# Cell_Monitor_12S_V0_1.net
KiCad netlist of a schematic drawn in Altium Designer
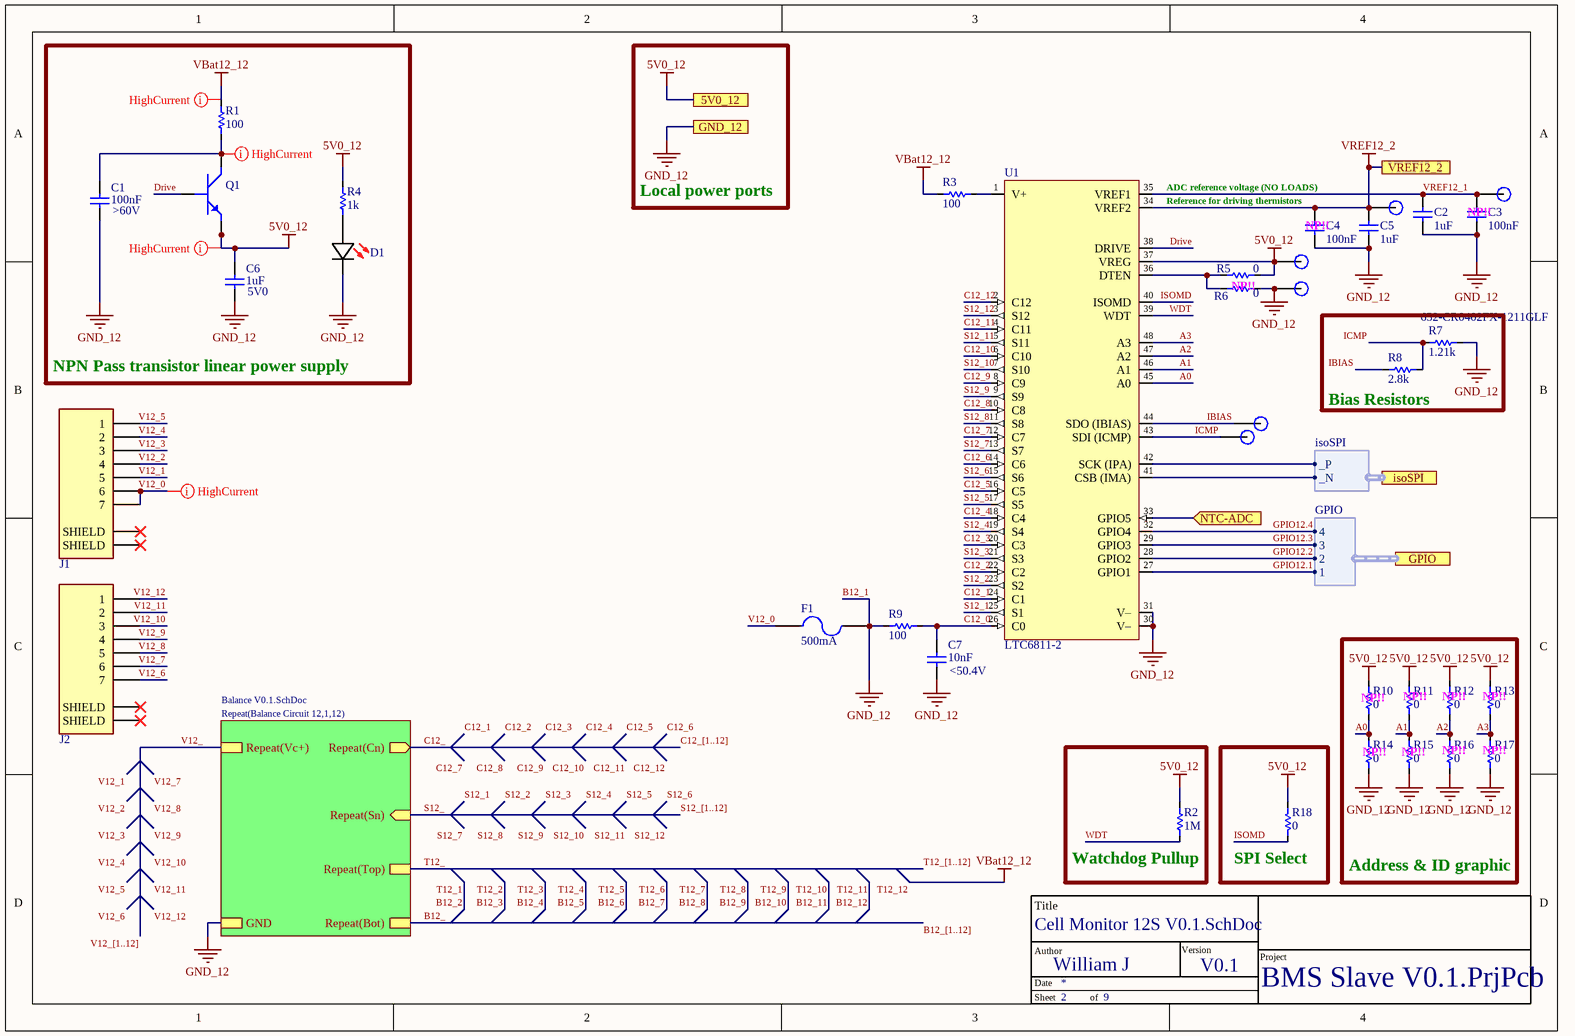
[diagram p0: Cell Monitor 12S V0.1.SchDoc]

(export (version "E")
  (design (tool "Eeschema 10.0.6"))
  (components
    (comp (ref "C1")
      (value "100nF")
      (footprint "C_0402")
      (description "Capacitor")
      (fields (field (name "VOLTAGE") ">60V") (field (name "Comment") "GRM155R62A104KE14D"))
      (libsource (lib "Passives") (part "Capacitor"))
    )
    (comp (ref "C2")
      (value "1uF")
      (footprint "C_0402")
      (description "Capacitor")
      (fields (field (name "Comment") "EMK105BJ105KV-F"))
      (libsource (lib "Passives") (part "Capacitor"))
    )
    (comp (ref "C3")
      (value "100nF")
      (footprint "C_0402")
      (description "Capacitor")
      (fields (field (name "Comment") "GRM155R62A104KE14D"))
      (libsource (lib "Passives") (part "Capacitor"))
    )
    (comp (ref "C4")
      (value "100nF")
      (footprint "C_0402")
      (description "Capacitor")
      (fields (field (name "Comment") "GRM155R62A104KE14D"))
      (libsource (lib "Passives") (part "Capacitor"))
    )
    (comp (ref "C5")
      (value "1uF")
      (footprint "C_0402")
      (description "Capacitor")
      (fields (field (name "Comment") "EMK105BJ105KV-F"))
      (libsource (lib "Passives") (part "Capacitor"))
    )
    (comp (ref "C6")
      (value "1uF")
      (footprint "C_0402")
      (description "Capacitor")
      (fields (field (name "VOLTAGE") "5V0") (field (name "Comment") "EMK105BJ105KV-F"))
      (libsource (lib "Passives") (part "Capacitor"))
    )
    (comp (ref "C7")
      (value "10nF")
      (footprint "C_0402")
      (description "Capacitor")
      (fields (field (name "VOLTAGE") "<50.4V") (field (name "Comment") "C1005X7S2A103K050BB"))
      (libsource (lib "Passives") (part "Capacitor"))
    )
    (comp (ref "D1")
      (value "150060SS55040")
      (footprint "LED (0603)")
      (description "LED RED DIFFUSED 0603 SMD")
      (fields (field (name "MANUFACTURER") "Wurth Electronics"))
      (libsource (lib "LEDLib") (part "150060SS55040"))
    )
    (comp (ref "F1")
      (value "0466.500NR")
      (footprint "0466.500NR")
      (fields
        (field (name "MANUFACTURER") "Littelfuse")
        (field (name "CURRENT RATING") "500mA")
        (field (name "PUBLISHER") "Altium Limited")
      )
      (libsource (lib "Miscellaneous Devices") (part "Fuse 2"))
    )
    (comp (ref "J1")
      (value "84953-7")
      (footprint "84953-7")
      (fields (field (name "MANUFACTURER") "TE Connectivity"))
      (libsource (lib "TE_Con") (part "84953-7"))
    )
    (comp (ref "J2")
      (value "84953-7")
      (footprint "84953-7")
      (fields (field (name "MANUFACTURER") "TE Connectivity"))
      (libsource (lib "TE_Con") (part "84953-7"))
    )
    (comp (ref "NT1") (value "NetTie") (footprint "NetTie") (libsource (lib "SchematicLib") (part "NetTie")))
    (comp (ref "NT2") (value "NetTie") (footprint "NetTie") (libsource (lib "SchematicLib") (part "NetTie")))
    (comp (ref "Q1")
      (value "PHPT60603NYX")
      (footprint "LFPAK56 (SOT669)")
      (description "60V, 3 A NPN high power bipolar transistor")
      (libsource (lib "SchematicLib") (part "PHPT60603NYX"))
    )
    (comp (ref "R1")
      (value "100")
      (footprint "R_2010")
      (description "Resistor")
      (fields (field (name "Comment") "CRM2010-FX-1000ELF"))
      (libsource (lib "Passives") (part "Resistor"))
    )
    (comp (ref "R2")
      (value "1M")
      (footprint "R_0402")
      (description "Resistor")
      (fields (field (name "Comment") "RC0402JR-071ML"))
      (libsource (lib "Passives") (part "Resistor"))
    )
    (comp (ref "R3")
      (value "100")
      (footprint "R_2010")
      (description "Resistor")
      (fields (field (name "Comment") "CRM2010-FX-1000ELF"))
      (libsource (lib "Passives") (part "Resistor"))
    )
    (comp (ref "R4")
      (value "1k")
      (footprint "R_0402")
      (description "Resistor")
      (fields (field (name "Comment") "RC0402FR-071KL"))
      (libsource (lib "Passives") (part "Resistor"))
    )
    (comp (ref "R5")
      (value "0")
      (footprint "R_0402")
      (description "Resistor")
      (fields (field (name "Comment") "CR0402-J/-000GLF"))
      (libsource (lib "Passives") (part "Resistor"))
    )
    (comp (ref "R6")
      (value "0")
      (footprint "R_0402")
      (description "Resistor")
      (fields (field (name "Comment") "CR0402-J/-000GLF"))
      (libsource (lib "Passives") (part "Resistor"))
    )
    (comp (ref "R7")
      (value "1.21k")
      (footprint "R_0402")
      (description "Resistor")
      (fields
        (field (name "SUPPLIER PART NUMBER 1") "652-CR0402FX-1211GLF")
        (field (name "Comment") "CR0402-FX-1211GLF")
      )
      (libsource (lib "Passives") (part "Resistor"))
    )
    (comp (ref "R8")
      (value "2.8k")
      (footprint "R_0402")
      (description "Resistor")
      (fields (field (name "Comment") "ERJ-2RKF2801X"))
      (libsource (lib "Passives") (part "Resistor"))
    )
    (comp (ref "R9")
      (value "100")
      (footprint "R_0402")
      (description "Resistor")
      (fields (field (name "Comment") "RC0402FR-07100RL"))
      (libsource (lib "Passives") (part "Resistor"))
    )
    (comp (ref "R10")
      (value "0")
      (footprint "R_0402")
      (description "Resistor")
      (fields (field (name "Comment") "CR0402-J/-000GLF"))
      (libsource (lib "Passives") (part "Resistor"))
    )
    (comp (ref "R11")
      (value "0")
      (footprint "R_0402")
      (description "Resistor")
      (fields (field (name "Comment") "CR0402-J/-000GLF"))
      (libsource (lib "Passives") (part "Resistor"))
    )
    (comp (ref "R12")
      (value "0")
      (footprint "R_0402")
      (description "Resistor")
      (fields (field (name "Comment") "CR0402-J/-000GLF"))
      (libsource (lib "Passives") (part "Resistor"))
    )
    (comp (ref "R13")
      (value "0")
      (footprint "R_0402")
      (description "Resistor")
      (fields (field (name "Comment") "CR0402-J/-000GLF"))
      (libsource (lib "Passives") (part "Resistor"))
    )
    (comp (ref "R14")
      (value "0")
      (footprint "R_0402")
      (description "Resistor")
      (fields (field (name "Comment") "CR0402-J/-000GLF"))
      (libsource (lib "Passives") (part "Resistor"))
    )
    (comp (ref "R15")
      (value "0")
      (footprint "R_0402")
      (description "Resistor")
      (fields (field (name "Comment") "CR0402-J/-000GLF"))
      (libsource (lib "Passives") (part "Resistor"))
    )
    (comp (ref "R16")
      (value "0")
      (footprint "R_0402")
      (description "Resistor")
      (fields (field (name "Comment") "CR0402-J/-000GLF"))
      (libsource (lib "Passives") (part "Resistor"))
    )
    (comp (ref "R17")
      (value "0")
      (footprint "R_0402")
      (description "Resistor")
      (fields (field (name "Comment") "CR0402-J/-000GLF"))
      (libsource (lib "Passives") (part "Resistor"))
    )
    (comp (ref "R18")
      (value "0")
      (footprint "R_0402")
      (description "Resistor")
      (fields (field (name "Comment") "CR0402-J/-000GLF"))
      (libsource (lib "Passives") (part "Resistor"))
    )
    (comp (ref "TP1")
      (value "VREF1")
      (footprint "Test Point")
      (description "1.2mm Test point")
      (libsource (lib "SchematicLib") (part "Test Point"))
    )
    (comp (ref "TP2")
      (value "VREF2")
      (footprint "Test Point")
      (description "1.2mm Test point")
      (libsource (lib "SchematicLib") (part "Test Point"))
    )
    (comp (ref "TP3")
      (value "5V0_12")
      (footprint "Test Point")
      (description "1.2mm Test point")
      (libsource (lib "SchematicLib") (part "Test Point"))
    )
    (comp (ref "TP4")
      (value "IBIAS")
      (footprint "Test Point")
      (description "1.2mm Test point")
      (libsource (lib "SchematicLib") (part "Test Point"))
    )
    (comp (ref "TP5")
      (value "ICMP")
      (footprint "Test Point")
      (description "1.2mm Test point")
      (libsource (lib "SchematicLib") (part "Test Point"))
    )
    (comp (ref "TP13")
      (value "5V0_8R")
      (footprint "Test Point")
      (description "1.2mm Test point")
      (libsource (lib "SchematicLib") (part "Test Point"))
    )
    (comp (ref "U1")
      (value "LTC6811-2")
      (footprint "SSOP50P780X200-48N")
      (description "12 Channel Multicell Battery Monitor with Addressable Interface")
      (libsource (lib "SchematicLib") (part "LTC6811-2"))
    )
  )
  (nets
    (net (code "3") (name "/A0") (class "Default")
      (node (ref "R10") (pin "1") (pinfunction "1_1") (pintype "passive"))
      (node (ref "R14") (pin "2") (pinfunction "2_2") (pintype "passive"))
      (node (ref "U1") (pin "45") (pinfunction "A0_45") (pintype "passive"))
    )
    (net (code "4") (name "/A1") (class "Default")
      (node (ref "R11") (pin "1") (pinfunction "1_1") (pintype "passive"))
      (node (ref "R15") (pin "2") (pinfunction "2_2") (pintype "passive"))
      (node (ref "U1") (pin "46") (pinfunction "A1_46") (pintype "passive"))
    )
    (net (code "5") (name "/A2") (class "Default")
      (node (ref "R12") (pin "1") (pinfunction "1_1") (pintype "passive"))
      (node (ref "R16") (pin "2") (pinfunction "2_2") (pintype "passive"))
      (node (ref "U1") (pin "47") (pinfunction "A2_47") (pintype "passive"))
    )
    (net (code "6") (name "/A3") (class "Default")
      (node (ref "R13") (pin "1") (pinfunction "1_1") (pintype "passive"))
      (node (ref "R17") (pin "2") (pinfunction "2_2") (pintype "passive"))
      (node (ref "U1") (pin "48") (pinfunction "A3_48") (pintype "passive"))
    )
    (net (code "8") (name "/B12_1") (class "Default") (node (ref "NT1") (pin "2") (pintype "passive")))
    (net (code "22") (name "/C12_0") (class "Default")
      (node (ref "C7") (pin "2") (pinfunction "2_2") (pintype "passive"))
      (node (ref "R9") (pin "2") (pinfunction "2_2") (pintype "passive"))
      (node (ref "U1") (pin "26") (pinfunction "C0_26") (pintype "input"))
    )
    (net (code "23") (name "/C12_1") (class "Default")
      (node (ref "U1") (pin "24") (pinfunction "C1_24") (pintype "input"))
    )
    (net (code "24") (name "/C12_2") (class "Default")
      (node (ref "U1") (pin "22") (pinfunction "C2_22") (pintype "input"))
    )
    (net (code "25") (name "/C12_3") (class "Default")
      (node (ref "U1") (pin "20") (pinfunction "C3_20") (pintype "input"))
    )
    (net (code "26") (name "/C12_4") (class "Default")
      (node (ref "U1") (pin "18") (pinfunction "C4_18") (pintype "input"))
    )
    (net (code "27") (name "/C12_5") (class "Default")
      (node (ref "U1") (pin "16") (pinfunction "C5_16") (pintype "input"))
    )
    (net (code "28") (name "/C12_6") (class "Default")
      (node (ref "U1") (pin "14") (pinfunction "C6_14") (pintype "input"))
    )
    (net (code "29") (name "/C12_7") (class "Default")
      (node (ref "U1") (pin "12") (pinfunction "C7_12") (pintype "input"))
    )
    (net (code "30") (name "/C12_8") (class "Default")
      (node (ref "U1") (pin "10") (pinfunction "C8_10") (pintype "input"))
    )
    (net (code "31") (name "/C12_9") (class "Default")
      (node (ref "U1") (pin "8") (pinfunction "C9_8") (pintype "input"))
    )
    (net (code "32") (name "/C12_10") (class "Default")
      (node (ref "U1") (pin "6") (pinfunction "C10_6") (pintype "input"))
    )
    (net (code "33") (name "/C12_11") (class "Default")
      (node (ref "U1") (pin "4") (pinfunction "C11_4") (pintype "input"))
    )
    (net (code "34") (name "/C12_12") (class "Default")
      (node (ref "U1") (pin "2") (pinfunction "C12_2") (pintype "input"))
    )
    (net (code "36") (name "/Drive") (class "Default")
      (node (ref "Q1") (pin "4") (pinfunction "Base_4") (pintype "passive"))
      (node (ref "U1") (pin "38") (pinfunction "DRIVE_38") (pintype "passive"))
    )
    (net (code "37") (name "/GPIO12.1") (class "Default")
      (node (ref "U1") (pin "27") (pinfunction "GPIO1_27") (pintype "bidirectional"))
    )
    (net (code "38") (name "/GPIO12.2") (class "Default")
      (node (ref "U1") (pin "28") (pinfunction "GPIO2_28") (pintype "bidirectional"))
    )
    (net (code "39") (name "/GPIO12.3") (class "Default")
      (node (ref "U1") (pin "29") (pinfunction "GPIO3_29") (pintype "bidirectional"))
    )
    (net (code "40") (name "/GPIO12.4") (class "Default")
      (node (ref "U1") (pin "32") (pinfunction "GPIO4_32") (pintype "bidirectional"))
    )
    (net (code "41") (name "/IBIAS") (class "Default")
      (node (ref "R8") (pin "1") (pinfunction "1_1") (pintype "passive"))
      (node (ref "TP4") (pin "1") (pinfunction "1_1") (pintype "passive"))
      (node (ref "U1") (pin "44") (pinfunction "SDO_(IBIAS)_44") (pintype "passive"))
    )
    (net (code "42") (name "/ICMP") (class "Default")
      (node (ref "R7") (pin "1") (pinfunction "1_1") (pintype "passive"))
      (node (ref "R8") (pin "2") (pinfunction "2_2") (pintype "passive"))
      (node (ref "TP5") (pin "1") (pinfunction "1_1") (pintype "passive"))
      (node (ref "U1") (pin "43") (pinfunction "SDI_(ICMP)_43") (pintype "passive"))
    )
    (net (code "43") (name "/ISOMD") (class "Default")
      (node (ref "R18") (pin "1") (pinfunction "1_1") (pintype "passive"))
      (node (ref "U1") (pin "40") (pinfunction "ISOMD_40") (pintype "passive"))
    )
    (net (code "44") (name "/NTC-ADC") (class "Default")
      (node (ref "U1") (pin "33") (pinfunction "GPIO5_33") (pintype "input"))
    )
    (net (code "46") (name "/S12_1") (class "Default")
      (node (ref "U1") (pin "25") (pinfunction "S1_25") (pintype "output"))
    )
    (net (code "47") (name "/S12_2") (class "Default")
      (node (ref "U1") (pin "23") (pinfunction "S2_23") (pintype "output"))
    )
    (net (code "48") (name "/S12_3") (class "Default")
      (node (ref "U1") (pin "21") (pinfunction "S3_21") (pintype "output"))
    )
    (net (code "49") (name "/S12_4") (class "Default")
      (node (ref "U1") (pin "19") (pinfunction "S4_19") (pintype "output"))
    )
    (net (code "50") (name "/S12_5") (class "Default")
      (node (ref "U1") (pin "17") (pinfunction "S5_17") (pintype "output"))
    )
    (net (code "51") (name "/S12_6") (class "Default")
      (node (ref "U1") (pin "15") (pinfunction "S6_15") (pintype "output"))
    )
    (net (code "52") (name "/S12_7") (class "Default")
      (node (ref "U1") (pin "13") (pinfunction "S7_13") (pintype "output"))
    )
    (net (code "53") (name "/S12_8") (class "Default")
      (node (ref "U1") (pin "11") (pinfunction "S8_11") (pintype "output"))
    )
    (net (code "54") (name "/S12_9") (class "Default")
      (node (ref "U1") (pin "9") (pinfunction "S9_9") (pintype "output"))
    )
    (net (code "55") (name "/S12_10") (class "Default")
      (node (ref "U1") (pin "7") (pinfunction "S10_7") (pintype "output"))
    )
    (net (code "56") (name "/S12_11") (class "Default")
      (node (ref "U1") (pin "5") (pinfunction "S11_5") (pintype "output"))
    )
    (net (code "57") (name "/S12_12") (class "Default")
      (node (ref "U1") (pin "3") (pinfunction "S12_3") (pintype "output"))
    )
    (net (code "60") (name "/T12_12") (class "Default") (node (ref "NT2") (pin "1") (pintype "passive")))
    (net (code "63") (name "/V12_0") (class "Default")
      (node (ref "F1") (pin "1") (pinfunction "1_1") (pintype "passive"))
      (node (ref "J1") (pin "6") (pinfunction "6_6") (pintype "passive"))
      (node (ref "J1") (pin "7") (pinfunction "7_7") (pintype "passive"))
    )
    (net (code "64") (name "/V12_1") (class "Default")
      (node (ref "J1") (pin "5") (pinfunction "5_5") (pintype "passive"))
    )
    (net (code "65") (name "/V12_2") (class "Default")
      (node (ref "J1") (pin "4") (pinfunction "4_4") (pintype "passive"))
    )
    (net (code "66") (name "/V12_3") (class "Default")
      (node (ref "J1") (pin "3") (pinfunction "3_3") (pintype "passive"))
    )
    (net (code "67") (name "/V12_4") (class "Default")
      (node (ref "J1") (pin "2") (pinfunction "2_2") (pintype "passive"))
    )
    (net (code "68") (name "/V12_5") (class "Default")
      (node (ref "J1") (pin "1") (pinfunction "1_1") (pintype "passive"))
    )
    (net (code "69") (name "/V12_6") (class "Default")
      (node (ref "J2") (pin "7") (pinfunction "7_7") (pintype "passive"))
    )
    (net (code "70") (name "/V12_7") (class "Default")
      (node (ref "J2") (pin "6") (pinfunction "6_6") (pintype "passive"))
    )
    (net (code "71") (name "/V12_8") (class "Default")
      (node (ref "J2") (pin "5") (pinfunction "5_5") (pintype "passive"))
    )
    (net (code "72") (name "/V12_9") (class "Default")
      (node (ref "J2") (pin "4") (pinfunction "4_4") (pintype "passive"))
    )
    (net (code "73") (name "/V12_10") (class "Default")
      (node (ref "J2") (pin "3") (pinfunction "3_3") (pintype "passive"))
    )
    (net (code "74") (name "/V12_11") (class "Default")
      (node (ref "J2") (pin "2") (pinfunction "2_2") (pintype "passive"))
    )
    (net (code "75") (name "/V12_12") (class "Default")
      (node (ref "J2") (pin "1") (pinfunction "1_1") (pintype "passive"))
    )
    (net (code "77") (name "/VREF12_1") (class "Default")
      (node (ref "C2") (pin "2") (pinfunction "2_2") (pintype "passive"))
      (node (ref "C3") (pin "2") (pinfunction "2_2") (pintype "passive"))
      (node (ref "TP1") (pin "1") (pinfunction "1_1") (pintype "passive"))
      (node (ref "U1") (pin "35") (pinfunction "VREF1_35") (pintype "power_in"))
    )
    (net (code "78") (name "/WDT") (class "Default")
      (node (ref "R2") (pin "1") (pinfunction "1_1") (pintype "passive"))
      (node (ref "U1") (pin "39") (pinfunction "WDT_39") (pintype "passive"))
    )
    (net (code "79") (name "/_N") (class "Default")
      (node (ref "U1") (pin "41") (pinfunction "CSB_(IMA)_41") (pintype "bidirectional"))
    )
    (net (code "80") (name "/_P") (class "Default")
      (node (ref "U1") (pin "42") (pinfunction "SCK_(IPA)_42") (pintype "bidirectional"))
    )
    (net (code "83") (name "5V0_12") (class "Default")
      (node (ref "C6") (pin "2") (pinfunction "2_2") (pintype "passive"))
      (node (ref "Q1") (pin "1") (pinfunction "Emitter_1") (pintype "passive"))
      (node (ref "Q1") (pin "2") (pinfunction "Emitter_2") (pintype "passive"))
      (node (ref "Q1") (pin "3") (pinfunction "Emitter_3") (pintype "passive"))
      (node (ref "R10") (pin "2") (pinfunction "2_2") (pintype "passive"))
      (node (ref "R11") (pin "2") (pinfunction "2_2") (pintype "passive"))
      (node (ref "R12") (pin "2") (pinfunction "2_2") (pintype "passive"))
      (node (ref "R13") (pin "2") (pinfunction "2_2") (pintype "passive"))
      (node (ref "R18") (pin "2") (pinfunction "2_2") (pintype "passive"))
      (node (ref "R2") (pin "2") (pinfunction "2_2") (pintype "passive"))
      (node (ref "R4") (pin "2") (pinfunction "2_2") (pintype "passive"))
      (node (ref "R5") (pin "2") (pinfunction "2_2") (pintype "passive"))
      (node (ref "TP3") (pin "1") (pinfunction "1_1") (pintype "passive"))
      (node (ref "U1") (pin "37") (pinfunction "VREG_37") (pintype "power_in"))
    )
    (net (code "84") (name "GND_12") (class "Default")
      (node (ref "C1") (pin "1") (pinfunction "1_1") (pintype "passive"))
      (node (ref "C2") (pin "1") (pinfunction "1_1") (pintype "passive"))
      (node (ref "C3") (pin "1") (pinfunction "1_1") (pintype "passive"))
      (node (ref "C4") (pin "1") (pinfunction "1_1") (pintype "passive"))
      (node (ref "C5") (pin "1") (pinfunction "1_1") (pintype "passive"))
      (node (ref "C6") (pin "1") (pinfunction "1_1") (pintype "passive"))
      (node (ref "C7") (pin "1") (pinfunction "1_1") (pintype "passive"))
      (node (ref "D1") (pin "1") (pinfunction "K_1") (pintype "passive"))
      (node (ref "F1") (pin "2") (pinfunction "2_2") (pintype "passive"))
      (node (ref "NT1") (pin "1") (pintype "passive"))
      (node (ref "R14") (pin "1") (pinfunction "1_1") (pintype "passive"))
      (node (ref "R15") (pin "1") (pinfunction "1_1") (pintype "passive"))
      (node (ref "R16") (pin "1") (pinfunction "1_1") (pintype "passive"))
      (node (ref "R17") (pin "1") (pinfunction "1_1") (pintype "passive"))
      (node (ref "R6") (pin "1") (pinfunction "1_1") (pintype "passive"))
      (node (ref "R7") (pin "2") (pinfunction "2_2") (pintype "passive"))
      (node (ref "R9") (pin "1") (pinfunction "1_1") (pintype "passive"))
      (node (ref "TP13") (pin "1") (pinfunction "1_1") (pintype "passive"))
      (node (ref "U1") (pin "30") (pinfunction "V–_30") (pintype "power_in"))
      (node (ref "U1") (pin "31") (pinfunction "V–_31") (pintype "power_in"))
    )
    (net (code "85") (name "Net-(D1-A)") (class "Default")
      (node (ref "D1") (pin "2") (pinfunction "A_2") (pintype "passive"))
      (node (ref "R4") (pin "1") (pinfunction "1_1") (pintype "passive"))
    )
    (net (code "86") (name "Net-(Q1-Collector)") (class "Default")
      (node (ref "C1") (pin "2") (pinfunction "2_2") (pintype "passive"))
      (node (ref "Q1") (pin "5") (pinfunction "Collector_5") (pintype "passive"))
      (node (ref "R1") (pin "1") (pinfunction "1_1") (pintype "passive"))
    )
    (net (code "87") (name "Net-(U1-DTEN)") (class "Default")
      (node (ref "R5") (pin "1") (pinfunction "1_1") (pintype "passive"))
      (node (ref "R6") (pin "2") (pinfunction "2_2") (pintype "passive"))
      (node (ref "U1") (pin "36") (pinfunction "DTEN_36") (pintype "passive"))
    )
    (net (code "88") (name "Net-(U1-V+)") (class "Default")
      (node (ref "R3") (pin "1") (pinfunction "1_1") (pintype "passive"))
      (node (ref "U1") (pin "1") (pinfunction "V+_1") (pintype "power_in"))
    )
    (net (code "89") (name "VBat12_12") (class "Default")
      (node (ref "NT2") (pin "2") (pintype "passive"))
      (node (ref "R1") (pin "2") (pinfunction "2_2") (pintype "passive"))
      (node (ref "R3") (pin "2") (pinfunction "2_2") (pintype "passive"))
    )
    (net (code "90") (name "VREF12_2") (class "Default")
      (node (ref "C4") (pin "2") (pinfunction "2_2") (pintype "passive"))
      (node (ref "C5") (pin "2") (pinfunction "2_2") (pintype "passive"))
      (node (ref "TP2") (pin "1") (pinfunction "1_1") (pintype "passive"))
      (node (ref "U1") (pin "34") (pinfunction "VREF2_34") (pintype "power_in"))
    )
    (net (code "91") (name "unconnected-(J1-SHIELD-PadS1)") (class "Default")
      (node (ref "J1") (pin "S1") (pinfunction "SHIELD_S1") (pintype "passive+no_connect"))
    )
    (net (code "92") (name "unconnected-(J1-SHIELD-PadS2)") (class "Default")
      (node (ref "J1") (pin "S2") (pinfunction "SHIELD_S2") (pintype "passive+no_connect"))
    )
    (net (code "93") (name "unconnected-(J2-SHIELD-PadS1)") (class "Default")
      (node (ref "J2") (pin "S1") (pinfunction "SHIELD_S1") (pintype "passive+no_connect"))
    )
    (net (code "94") (name "unconnected-(J2-SHIELD-PadS2)") (class "Default")
      (node (ref "J2") (pin "S2") (pinfunction "SHIELD_S2") (pintype "passive+no_connect"))
    )
  )
)
